# EPS_Battery_Controller_Diode.net
KiCad netlist of a schematic drawn in Altium Designer
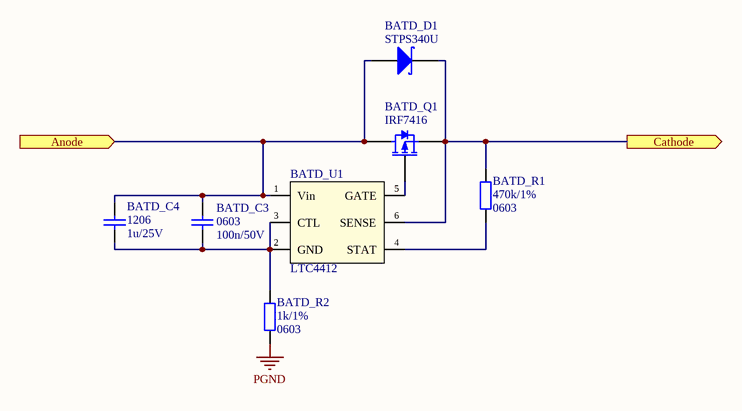
[diagram p0: EPS_Battery_Controller_Diode.SchDoc]

(export (version "E")
  (design (tool "Eeschema 10.0.6"))
  (components
    (comp (ref "BATD_C3")
      (value "100n/50V")
      (footprint "SMD_Capacitor_0603")
      (description "Ceramic Cap Murata Automotive 100n/50V X7R 0603")
      (fields
        (field (name "MANUFACTURER") "Murata")
        (field (name "MANUFACTURERPARTNUMBER") "GCJ188R71H104KA12D")
        (field (name "PACKAGE") "0603")
      )
      (libsource (lib "capacitors") (part "Cer_GCJ188R71H104KA12D"))
    )
    (comp (ref "BATD_C4")
      (value "1u/25V")
      (footprint "SMD_Capacitor_1206")
      (description "Ceramic Cap Kemet COTS 1u/25V X7R 1206")
      (fields
        (field (name "MANUFACTURERPARTNUMBER") "C1206T105K3RALTU")
        (field (name "MANUFACTURER") "Kemet")
        (field (name "PACKAGE") "1206")
      )
      (libsource (lib "capacitors") (part "Cer_C1206T105K3RALTU"))
    )
    (comp (ref "BATD_D1")
      (value "STPS340U")
      (footprint "DO-214AA")
      (description "3A/40V Power Schottky Rectifier.")
      (fields (field (name "MANUFACTURER") "STMicroelectronics"))
      (libsource (lib "diodes") (part "STPS340x"))
    )
    (comp (ref "BATD_Q1")
      (value "IRF7416")
      (footprint "SOIC-8-N_SSSGDDDD")
      (description "10A/30V HEXFET Power P-MOSFET.")
      (fields (field (name "MANUFACTURER") "International Rectifier"))
      (libsource (lib "transistors") (part "IRF7416"))
    )
    (comp (ref "BATD_R1")
      (value "470k/1%")
      (footprint "SMD_Resistor_0603")
      (fields (field (name "PACKAGE") "0603"))
      (libsource (lib "resistors") (part "Res"))
    )
    (comp (ref "BATD_R2")
      (value "1k/1%")
      (footprint "SMD_Resistor_0603")
      (fields (field (name "PACKAGE") "0603"))
      (libsource (lib "resistors") (part "Res"))
    )
    (comp (ref "BATD_U1")
      (value "LTC4412")
      (footprint "SOT23-6")
      (description "Ideal Diode, Low Loss PowerPath Controller.")
      (fields (field (name "MANUFACTURER") "Linear Technology"))
      (libsource (lib "microcircuits") (part "LTC4412"))
    )
  )
  (nets
    (net (code "1") (name "/Anode") (class "Default")
      (node (ref "BATD_C3") (pin "1") (pinfunction "1_1") (pintype "passive"))
      (node (ref "BATD_C4") (pin "1") (pinfunction "1_1") (pintype "passive"))
      (node (ref "BATD_D1") (pin "A") (pinfunction "A_A") (pintype "passive"))
      (node (ref "BATD_Q1") (pin "D") (pinfunction "D_D") (pintype "passive"))
      (node (ref "BATD_U1") (pin "1") (pinfunction "Vin_1") (pintype "passive"))
    )
    (net (code "2") (name "/Cathode") (class "Default")
      (node (ref "BATD_D1") (pin "K") (pinfunction "K_K") (pintype "passive"))
      (node (ref "BATD_Q1") (pin "S") (pinfunction "S_S") (pintype "passive"))
      (node (ref "BATD_R1") (pin "1") (pinfunction "1_1") (pintype "passive"))
      (node (ref "BATD_U1") (pin "6") (pinfunction "SENSE_6") (pintype "passive"))
    )
    (net (code "3") (name "Net-(BATD_U1-CTL)") (class "Default")
      (node (ref "BATD_C3") (pin "2") (pinfunction "2_2") (pintype "passive"))
      (node (ref "BATD_C4") (pin "2") (pinfunction "2_2") (pintype "passive"))
      (node (ref "BATD_R2") (pin "1") (pinfunction "1_1") (pintype "passive"))
      (node (ref "BATD_U1") (pin "2") (pinfunction "GND_2") (pintype "passive"))
      (node (ref "BATD_U1") (pin "3") (pinfunction "CTL_3") (pintype "passive"))
    )
    (net (code "4") (name "Net-(BATD_U1-GATE)") (class "Default")
      (node (ref "BATD_Q1") (pin "G") (pinfunction "G_G") (pintype "passive"))
      (node (ref "BATD_U1") (pin "5") (pinfunction "GATE_5") (pintype "passive"))
    )
    (net (code "5") (name "Net-(BATD_U1-STAT)") (class "Default")
      (node (ref "BATD_R1") (pin "2") (pinfunction "2_2") (pintype "passive"))
      (node (ref "BATD_U1") (pin "4") (pinfunction "STAT_4") (pintype "passive"))
    )
    (net (code "6") (name "PGND") (class "Default")
      (node (ref "BATD_R2") (pin "2") (pinfunction "2_2") (pintype "passive"))
    )
  )
)
